# Input_dig.net
KiCad netlist of a schematic drawn in Altium Designer
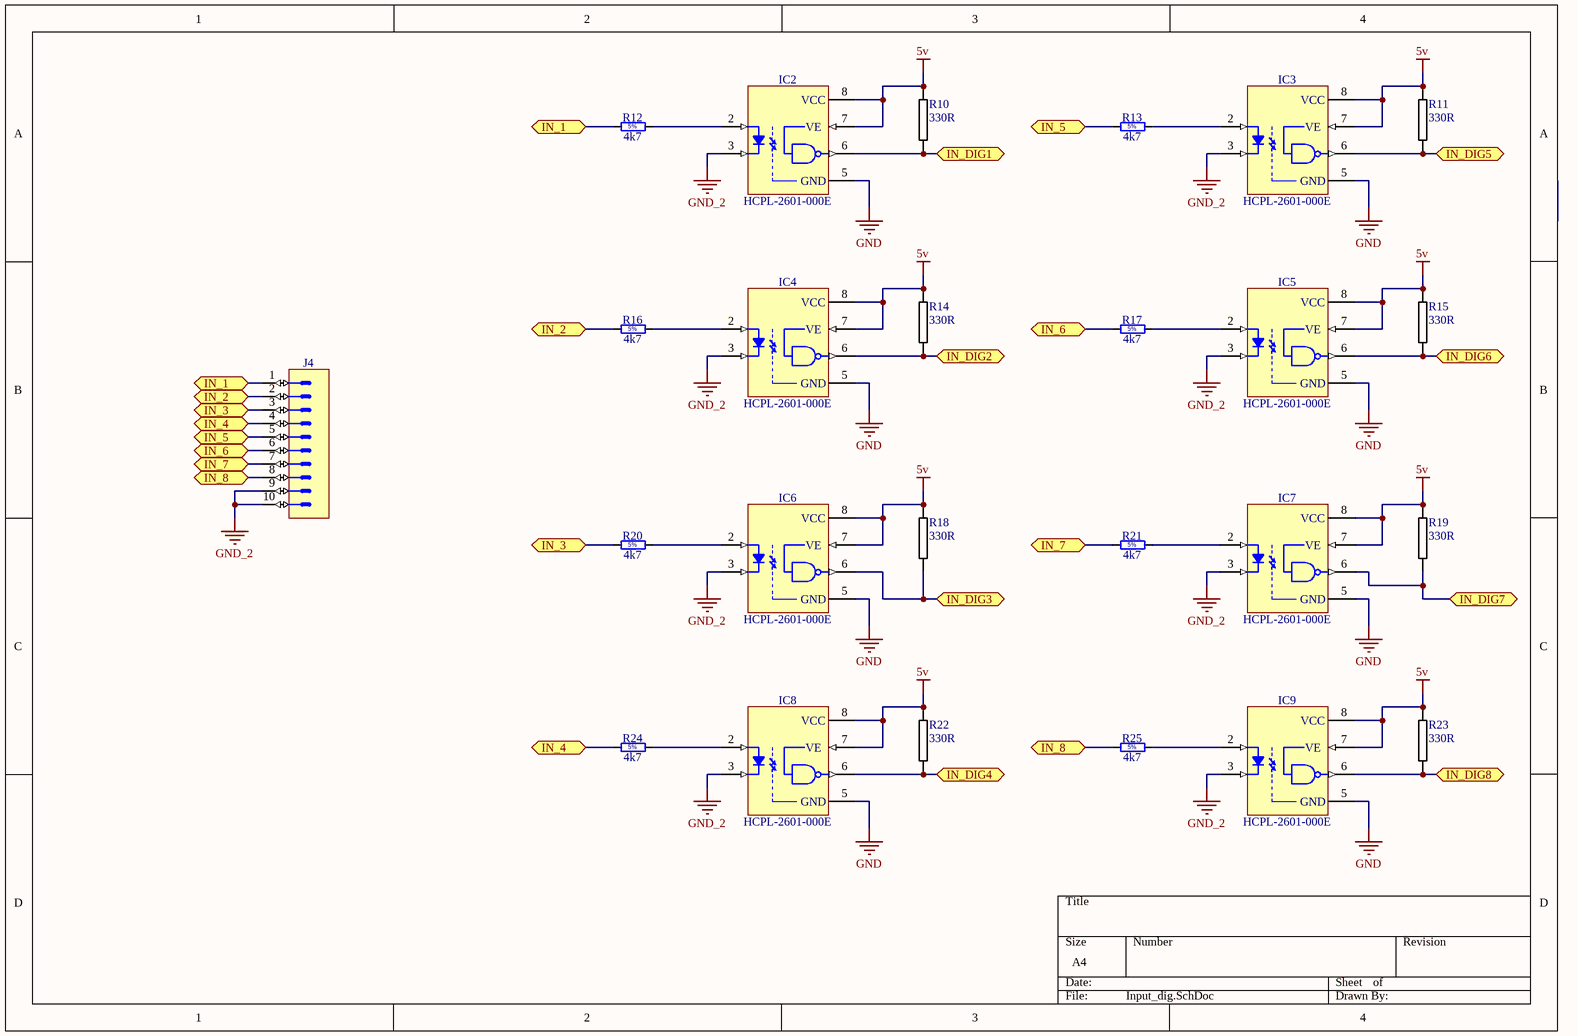
[diagram p0: Input_dig.SchDoc]

(export (version "E")
  (design (tool "Eeschema 10.0.6"))
  (components
    (comp (ref "IC2")
      (value "HCPL-2601-000E")
      (footprint "DIP8-300")
      (description "Single Optocoupler")
      (fields (field (name "MANUFACTURER") "AVAGO TECHNOLOGIES") (field (name "AUTHOR") "CERN DEM JLC"))
      (libsource (lib "ICs And Semiconductors") (part "Optocoupler Type8"))
    )
    (comp (ref "IC3")
      (value "HCPL-2601-000E")
      (footprint "DIP8-300")
      (description "Single Optocoupler")
      (fields (field (name "MANUFACTURER") "AVAGO TECHNOLOGIES") (field (name "AUTHOR") "CERN DEM JLC"))
      (libsource (lib "ICs And Semiconductors") (part "Optocoupler Type8"))
    )
    (comp (ref "IC4")
      (value "HCPL-2601-000E")
      (footprint "DIP8-300")
      (description "Single Optocoupler")
      (fields (field (name "MANUFACTURER") "AVAGO TECHNOLOGIES") (field (name "AUTHOR") "CERN DEM JLC"))
      (libsource (lib "ICs And Semiconductors") (part "Optocoupler Type8"))
    )
    (comp (ref "IC5")
      (value "HCPL-2601-000E")
      (footprint "DIP8-300")
      (description "Single Optocoupler")
      (fields (field (name "MANUFACTURER") "AVAGO TECHNOLOGIES") (field (name "AUTHOR") "CERN DEM JLC"))
      (libsource (lib "ICs And Semiconductors") (part "Optocoupler Type8"))
    )
    (comp (ref "IC6")
      (value "HCPL-2601-000E")
      (footprint "DIP8-300")
      (description "Single Optocoupler")
      (fields (field (name "MANUFACTURER") "AVAGO TECHNOLOGIES") (field (name "AUTHOR") "CERN DEM JLC"))
      (libsource (lib "ICs And Semiconductors") (part "Optocoupler Type8"))
    )
    (comp (ref "IC7")
      (value "HCPL-2601-000E")
      (footprint "DIP8-300")
      (description "Single Optocoupler")
      (fields (field (name "MANUFACTURER") "AVAGO TECHNOLOGIES") (field (name "AUTHOR") "CERN DEM JLC"))
      (libsource (lib "ICs And Semiconductors") (part "Optocoupler Type8"))
    )
    (comp (ref "IC8")
      (value "HCPL-2601-000E")
      (footprint "DIP8-300")
      (description "Single Optocoupler")
      (fields (field (name "MANUFACTURER") "AVAGO TECHNOLOGIES") (field (name "AUTHOR") "CERN DEM JLC"))
      (libsource (lib "ICs And Semiconductors") (part "Optocoupler Type8"))
    )
    (comp (ref "IC9")
      (value "HCPL-2601-000E")
      (footprint "DIP8-300")
      (description "Single Optocoupler")
      (fields (field (name "MANUFACTURER") "AVAGO TECHNOLOGIES") (field (name "AUTHOR") "CERN DEM JLC"))
      (libsource (lib "ICs And Semiconductors") (part "Optocoupler Type8"))
    )
    (comp (ref "J4")
      (value "~")
      (footprint "PHOENIX_1757323")
      (description "Connector 10 Male")
      (fields
        (field (name "PART NUMBER") "PHOENIX_1757323")
        (field (name "MANUFACTURER") "PHOENIX CONTACT")
        (field (name "AUTHOR") "CERN DEM JLC")
      )
      (libsource (lib "Connectors") (part "Connector 10 Male"))
    )
    (comp (ref "R10")
      (value "330R")
      (footprint "0805R-330")
      (description "RESISTOR 0805 1/4 WATT THIN FILM")
      (libsource (lib "vh_altium_library") (part "0805R-330"))
    )
    (comp (ref "R11")
      (value "330R")
      (footprint "0805R-330")
      (description "RESISTOR 0805 1/4 WATT THIN FILM")
      (libsource (lib "vh_altium_library") (part "0805R-330"))
    )
    (comp (ref "R12")
      (value "4k7")
      (footprint "RES2286-1670X520")
      (description "Resistor - 5%")
      (fields
        (field (name "PART NUMBER") "RMF_4K7_5%_3W_250PPM_2286-1670X520")
        (field (name "POWER") "3W")
        (field (name "AUTHOR") "CERN DEM JLC")
      )
      (libsource (lib "Resistors") (part "Resistor - 5%"))
    )
    (comp (ref "R13")
      (value "4k7")
      (footprint "RES2286-1670X520")
      (description "Resistor - 5%")
      (fields
        (field (name "PART NUMBER") "RMF_4K7_5%_3W_250PPM_2286-1670X520")
        (field (name "POWER") "3W")
        (field (name "AUTHOR") "CERN DEM JLC")
      )
      (libsource (lib "Resistors") (part "Resistor - 5%"))
    )
    (comp (ref "R14")
      (value "330R")
      (footprint "0805R-330")
      (description "RESISTOR 0805 1/4 WATT THIN FILM")
      (libsource (lib "vh_altium_library") (part "0805R-330"))
    )
    (comp (ref "R15")
      (value "330R")
      (footprint "0805R-330")
      (description "RESISTOR 0805 1/4 WATT THIN FILM")
      (libsource (lib "vh_altium_library") (part "0805R-330"))
    )
    (comp (ref "R16")
      (value "4k7")
      (footprint "RES2286-1670X520")
      (description "Resistor - 5%")
      (fields
        (field (name "PART NUMBER") "RMF_4K7_5%_3W_250PPM_2286-1670X520")
        (field (name "POWER") "3W")
        (field (name "AUTHOR") "CERN DEM JLC")
      )
      (libsource (lib "Resistors") (part "Resistor - 5%"))
    )
    (comp (ref "R17")
      (value "4k7")
      (footprint "RES2286-1670X520")
      (description "Resistor - 5%")
      (fields
        (field (name "PART NUMBER") "RMF_4K7_5%_3W_250PPM_2286-1670X520")
        (field (name "POWER") "3W")
        (field (name "AUTHOR") "CERN DEM JLC")
      )
      (libsource (lib "Resistors") (part "Resistor - 5%"))
    )
    (comp (ref "R18")
      (value "330R")
      (footprint "0805R-330")
      (description "RESISTOR 0805 1/4 WATT THIN FILM")
      (libsource (lib "vh_altium_library") (part "0805R-330"))
    )
    (comp (ref "R19")
      (value "330R")
      (footprint "0805R-330")
      (description "RESISTOR 0805 1/4 WATT THIN FILM")
      (libsource (lib "vh_altium_library") (part "0805R-330"))
    )
    (comp (ref "R20")
      (value "4k7")
      (footprint "RES2286-1670X520")
      (description "Resistor - 5%")
      (fields
        (field (name "PART NUMBER") "RMF_4K7_5%_3W_250PPM_2286-1670X520")
        (field (name "POWER") "3W")
        (field (name "AUTHOR") "CERN DEM JLC")
      )
      (libsource (lib "Resistors") (part "Resistor - 5%"))
    )
    (comp (ref "R21")
      (value "4k7")
      (footprint "RES2286-1670X520")
      (description "Resistor - 5%")
      (fields
        (field (name "PART NUMBER") "RMF_4K7_5%_3W_250PPM_2286-1670X520")
        (field (name "POWER") "3W")
        (field (name "AUTHOR") "CERN DEM JLC")
      )
      (libsource (lib "Resistors") (part "Resistor - 5%"))
    )
    (comp (ref "R22")
      (value "330R")
      (footprint "0805R-330")
      (description "RESISTOR 0805 1/4 WATT THIN FILM")
      (libsource (lib "vh_altium_library") (part "0805R-330"))
    )
    (comp (ref "R23")
      (value "330R")
      (footprint "0805R-330")
      (description "RESISTOR 0805 1/4 WATT THIN FILM")
      (libsource (lib "vh_altium_library") (part "0805R-330"))
    )
    (comp (ref "R24")
      (value "4k7")
      (footprint "RES2286-1670X520")
      (description "Resistor - 5%")
      (fields
        (field (name "PART NUMBER") "RMF_4K7_5%_3W_250PPM_2286-1670X520")
        (field (name "POWER") "3W")
        (field (name "AUTHOR") "CERN DEM JLC")
      )
      (libsource (lib "Resistors") (part "Resistor - 5%"))
    )
    (comp (ref "R25")
      (value "4k7")
      (footprint "RES2286-1670X520")
      (description "Resistor - 5%")
      (fields
        (field (name "PART NUMBER") "RMF_4K7_5%_3W_250PPM_2286-1670X520")
        (field (name "POWER") "3W")
        (field (name "AUTHOR") "CERN DEM JLC")
      )
      (libsource (lib "Resistors") (part "Resistor - 5%"))
    )
  )
  (nets
    (net (code "1") (name "/IN_1") (class "Default")
      (node (ref "J4") (pin "1") (pinfunction "1_1") (pintype "bidirectional"))
      (node (ref "R12") (pin "1") (pinfunction "1_1") (pintype "passive"))
    )
    (net (code "2") (name "/IN_2") (class "Default")
      (node (ref "J4") (pin "2") (pinfunction "2_2") (pintype "bidirectional"))
      (node (ref "R16") (pin "1") (pinfunction "1_1") (pintype "passive"))
    )
    (net (code "3") (name "/IN_3") (class "Default")
      (node (ref "J4") (pin "3") (pinfunction "3_3") (pintype "bidirectional"))
      (node (ref "R20") (pin "1") (pinfunction "1_1") (pintype "passive"))
    )
    (net (code "4") (name "/IN_4") (class "Default")
      (node (ref "J4") (pin "4") (pinfunction "4_4") (pintype "bidirectional"))
      (node (ref "R24") (pin "1") (pinfunction "1_1") (pintype "passive"))
    )
    (net (code "5") (name "/IN_5") (class "Default")
      (node (ref "J4") (pin "5") (pinfunction "5_5") (pintype "bidirectional"))
      (node (ref "R13") (pin "1") (pinfunction "1_1") (pintype "passive"))
    )
    (net (code "6") (name "/IN_6") (class "Default")
      (node (ref "J4") (pin "6") (pinfunction "6_6") (pintype "bidirectional"))
      (node (ref "R17") (pin "1") (pinfunction "1_1") (pintype "passive"))
    )
    (net (code "7") (name "/IN_7") (class "Default")
      (node (ref "J4") (pin "7") (pinfunction "7_7") (pintype "bidirectional"))
      (node (ref "R21") (pin "1") (pinfunction "1_1") (pintype "passive"))
    )
    (net (code "8") (name "/IN_8") (class "Default")
      (node (ref "J4") (pin "8") (pinfunction "8_8") (pintype "bidirectional"))
      (node (ref "R25") (pin "1") (pinfunction "1_1") (pintype "passive"))
    )
    (net (code "9") (name "/IN_DIG1") (class "Default")
      (node (ref "IC2") (pin "6") (pinfunction "VO_6") (pintype "output"))
      (node (ref "R10") (pin "2") (pintype "passive"))
    )
    (net (code "10") (name "/IN_DIG2") (class "Default")
      (node (ref "IC4") (pin "6") (pinfunction "VO_6") (pintype "output"))
      (node (ref "R14") (pin "2") (pintype "passive"))
    )
    (net (code "11") (name "/IN_DIG3") (class "Default")
      (node (ref "IC6") (pin "6") (pinfunction "VO_6") (pintype "output"))
      (node (ref "R18") (pin "2") (pintype "passive"))
    )
    (net (code "12") (name "/IN_DIG4") (class "Default")
      (node (ref "IC8") (pin "6") (pinfunction "VO_6") (pintype "output"))
      (node (ref "R22") (pin "2") (pintype "passive"))
    )
    (net (code "13") (name "/IN_DIG5") (class "Default")
      (node (ref "IC3") (pin "6") (pinfunction "VO_6") (pintype "output"))
      (node (ref "R11") (pin "2") (pintype "passive"))
    )
    (net (code "14") (name "/IN_DIG6") (class "Default")
      (node (ref "IC5") (pin "6") (pinfunction "VO_6") (pintype "output"))
      (node (ref "R15") (pin "2") (pintype "passive"))
    )
    (net (code "15") (name "/IN_DIG7") (class "Default")
      (node (ref "IC7") (pin "6") (pinfunction "VO_6") (pintype "output"))
      (node (ref "R19") (pin "2") (pintype "passive"))
    )
    (net (code "16") (name "/IN_DIG8") (class "Default")
      (node (ref "IC9") (pin "6") (pinfunction "VO_6") (pintype "output"))
      (node (ref "R23") (pin "2") (pintype "passive"))
    )
    (net (code "17") (name "5v") (class "Default")
      (node (ref "IC2") (pin "7") (pinfunction "VE_7") (pintype "input"))
      (node (ref "IC2") (pin "8") (pinfunction "VCC_8") (pintype "power_in"))
      (node (ref "IC3") (pin "7") (pinfunction "VE_7") (pintype "input"))
      (node (ref "IC3") (pin "8") (pinfunction "VCC_8") (pintype "power_in"))
      (node (ref "IC4") (pin "7") (pinfunction "VE_7") (pintype "input"))
      (node (ref "IC4") (pin "8") (pinfunction "VCC_8") (pintype "power_in"))
      (node (ref "IC5") (pin "7") (pinfunction "VE_7") (pintype "input"))
      (node (ref "IC5") (pin "8") (pinfunction "VCC_8") (pintype "power_in"))
      (node (ref "IC6") (pin "7") (pinfunction "VE_7") (pintype "input"))
      (node (ref "IC6") (pin "8") (pinfunction "VCC_8") (pintype "power_in"))
      (node (ref "IC7") (pin "7") (pinfunction "VE_7") (pintype "input"))
      (node (ref "IC7") (pin "8") (pinfunction "VCC_8") (pintype "power_in"))
      (node (ref "IC8") (pin "7") (pinfunction "VE_7") (pintype "input"))
      (node (ref "IC8") (pin "8") (pinfunction "VCC_8") (pintype "power_in"))
      (node (ref "IC9") (pin "7") (pinfunction "VE_7") (pintype "input"))
      (node (ref "IC9") (pin "8") (pinfunction "VCC_8") (pintype "power_in"))
      (node (ref "R10") (pin "1") (pintype "passive"))
      (node (ref "R11") (pin "1") (pintype "passive"))
      (node (ref "R14") (pin "1") (pintype "passive"))
      (node (ref "R15") (pin "1") (pintype "passive"))
      (node (ref "R18") (pin "1") (pintype "passive"))
      (node (ref "R19") (pin "1") (pintype "passive"))
      (node (ref "R22") (pin "1") (pintype "passive"))
      (node (ref "R23") (pin "1") (pintype "passive"))
    )
    (net (code "18") (name "GND") (class "Default")
      (node (ref "IC2") (pin "5") (pinfunction "GND_5") (pintype "power_in"))
      (node (ref "IC3") (pin "5") (pinfunction "GND_5") (pintype "power_in"))
      (node (ref "IC4") (pin "5") (pinfunction "GND_5") (pintype "power_in"))
      (node (ref "IC5") (pin "5") (pinfunction "GND_5") (pintype "power_in"))
      (node (ref "IC6") (pin "5") (pinfunction "GND_5") (pintype "power_in"))
      (node (ref "IC7") (pin "5") (pinfunction "GND_5") (pintype "power_in"))
      (node (ref "IC8") (pin "5") (pinfunction "GND_5") (pintype "power_in"))
      (node (ref "IC9") (pin "5") (pinfunction "GND_5") (pintype "power_in"))
    )
    (net (code "19") (name "GND_2") (class "Default")
      (node (ref "IC2") (pin "3") (pinfunction "K_3") (pintype "input"))
      (node (ref "IC3") (pin "3") (pinfunction "K_3") (pintype "input"))
      (node (ref "IC4") (pin "3") (pinfunction "K_3") (pintype "input"))
      (node (ref "IC5") (pin "3") (pinfunction "K_3") (pintype "input"))
      (node (ref "IC6") (pin "3") (pinfunction "K_3") (pintype "input"))
      (node (ref "IC7") (pin "3") (pinfunction "K_3") (pintype "input"))
      (node (ref "IC8") (pin "3") (pinfunction "K_3") (pintype "input"))
      (node (ref "IC9") (pin "3") (pinfunction "K_3") (pintype "input"))
      (node (ref "J4") (pin "10") (pinfunction "10_10") (pintype "bidirectional"))
      (node (ref "J4") (pin "9") (pinfunction "9_9") (pintype "bidirectional"))
    )
    (net (code "20") (name "Net-(IC2-A)") (class "Default")
      (node (ref "IC2") (pin "2") (pinfunction "A_2") (pintype "input"))
      (node (ref "R12") (pin "2") (pinfunction "2_2") (pintype "passive"))
    )
    (net (code "21") (name "Net-(IC3-A)") (class "Default")
      (node (ref "IC3") (pin "2") (pinfunction "A_2") (pintype "input"))
      (node (ref "R13") (pin "2") (pinfunction "2_2") (pintype "passive"))
    )
    (net (code "22") (name "Net-(IC4-A)") (class "Default")
      (node (ref "IC4") (pin "2") (pinfunction "A_2") (pintype "input"))
      (node (ref "R16") (pin "2") (pinfunction "2_2") (pintype "passive"))
    )
    (net (code "23") (name "Net-(IC5-A)") (class "Default")
      (node (ref "IC5") (pin "2") (pinfunction "A_2") (pintype "input"))
      (node (ref "R17") (pin "2") (pinfunction "2_2") (pintype "passive"))
    )
    (net (code "24") (name "Net-(IC6-A)") (class "Default")
      (node (ref "IC6") (pin "2") (pinfunction "A_2") (pintype "input"))
      (node (ref "R20") (pin "2") (pinfunction "2_2") (pintype "passive"))
    )
    (net (code "25") (name "Net-(IC7-A)") (class "Default")
      (node (ref "IC7") (pin "2") (pinfunction "A_2") (pintype "input"))
      (node (ref "R21") (pin "2") (pinfunction "2_2") (pintype "passive"))
    )
    (net (code "26") (name "Net-(IC8-A)") (class "Default")
      (node (ref "IC8") (pin "2") (pinfunction "A_2") (pintype "input"))
      (node (ref "R24") (pin "2") (pinfunction "2_2") (pintype "passive"))
    )
    (net (code "27") (name "Net-(IC9-A)") (class "Default")
      (node (ref "IC9") (pin "2") (pinfunction "A_2") (pintype "input"))
      (node (ref "R25") (pin "2") (pinfunction "2_2") (pintype "passive"))
    )
  )
)
